# i-o_pines.net
KiCad netlist of a schematic drawn in Altium Designer
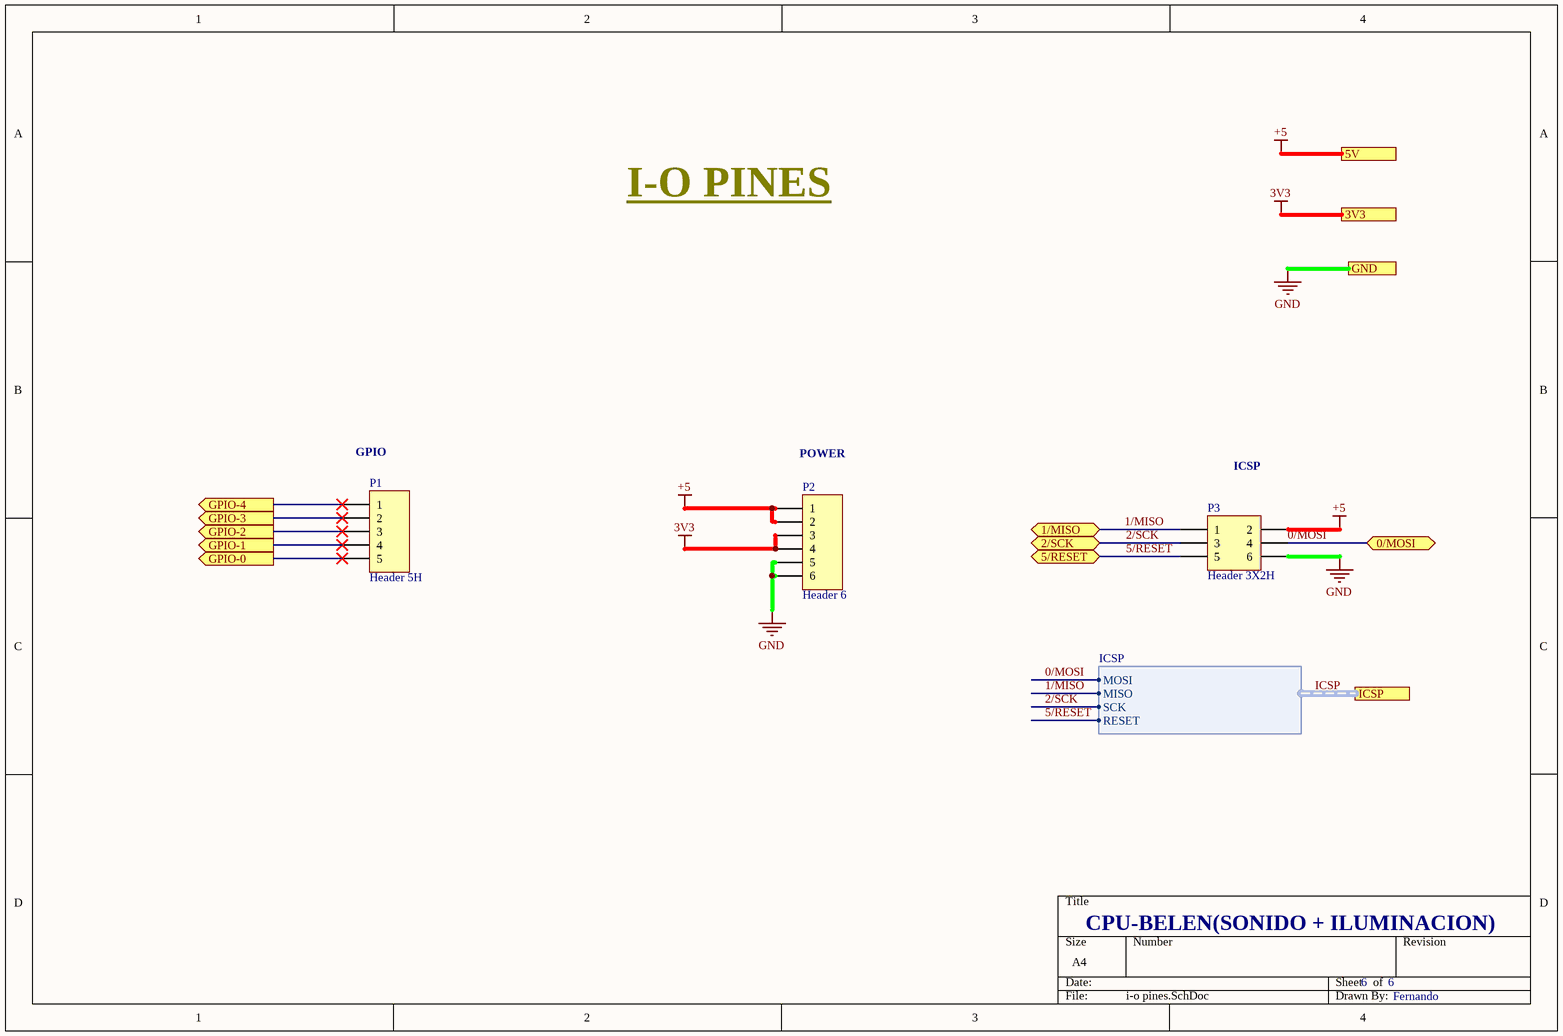
[diagram p0: i-o pines.SchDoc]

(export (version "E")
  (design (tool "Eeschema 10.0.6"))
  (components
    (comp (ref "P1")
      (value "Header 5H")
      (footprint "HDR1X5")
      (description "Header, 5-Pin, Right Angle")
      (fields (field (name "PUBLISHER") "Altium Limited"))
      (libsource (lib "Miscellaneous Connectors") (part "Header 5H"))
    )
    (comp (ref "P2")
      (value "Header 6")
      (footprint "HDR1X6")
      (description "Header, 6-Pin")
      (fields (field (name "PUBLISHER") "Altium Limited"))
      (libsource (lib "Miscellaneous Connectors") (part "Header 6"))
    )
    (comp (ref "P3")
      (value "Header 3X2H")
      (footprint "HDR2X3")
      (description "Header, 3-Pin, Dual row, Right Angle")
      (fields (field (name "PUBLISHER") "Altium Limited"))
      (libsource (lib "Miscellaneous Connectors") (part "Header 3X2H"))
    )
  )
  (nets
    (net (code "2") (name "+5") (class "Default")
      (node (ref "P2") (pin "1") (pinfunction "1_1") (pintype "passive"))
      (node (ref "P2") (pin "2") (pinfunction "2_2") (pintype "passive"))
      (node (ref "P3") (pin "2") (pinfunction "2_2") (pintype "passive"))
    )
    (net (code "3") (name "/0{slash}MOSI") (class "Default")
      (node (ref "P3") (pin "4") (pinfunction "4_4") (pintype "passive"))
    )
    (net (code "4") (name "/1{slash}MISO") (class "Default")
      (node (ref "P3") (pin "1") (pinfunction "1_1") (pintype "passive"))
    )
    (net (code "5") (name "/2{slash}SCK") (class "Default")
      (node (ref "P3") (pin "3") (pinfunction "3_3") (pintype "passive"))
    )
    (net (code "6") (name "/5{slash}RESET") (class "Default")
      (node (ref "P3") (pin "5") (pinfunction "5_5") (pintype "passive"))
    )
    (net (code "7") (name "/GPIO-0") (class "Default")
      (node (ref "P1") (pin "5") (pinfunction "5_5") (pintype "passive+no_connect"))
    )
    (net (code "8") (name "/GPIO-1") (class "Default")
      (node (ref "P1") (pin "4") (pinfunction "4_4") (pintype "passive+no_connect"))
    )
    (net (code "9") (name "/GPIO-2") (class "Default")
      (node (ref "P1") (pin "3") (pinfunction "3_3") (pintype "passive+no_connect"))
    )
    (net (code "10") (name "/GPIO-3") (class "Default")
      (node (ref "P1") (pin "2") (pinfunction "2_2") (pintype "passive+no_connect"))
    )
    (net (code "11") (name "/GPIO-4") (class "Default")
      (node (ref "P1") (pin "1") (pinfunction "1_1") (pintype "passive+no_connect"))
    )
    (net (code "13") (name "3V3") (class "Default")
      (node (ref "P2") (pin "3") (pinfunction "3_3") (pintype "passive"))
      (node (ref "P2") (pin "4") (pinfunction "4_4") (pintype "passive"))
    )
    (net (code "14") (name "GND") (class "Default")
      (node (ref "P2") (pin "5") (pinfunction "5_5") (pintype "passive"))
      (node (ref "P2") (pin "6") (pinfunction "6_6") (pintype "passive"))
      (node (ref "P3") (pin "6") (pinfunction "6_6") (pintype "passive"))
    )
  )
)
